# reference_2v5_LTC6655.net
KiCad netlist of a schematic drawn in Altium Designer
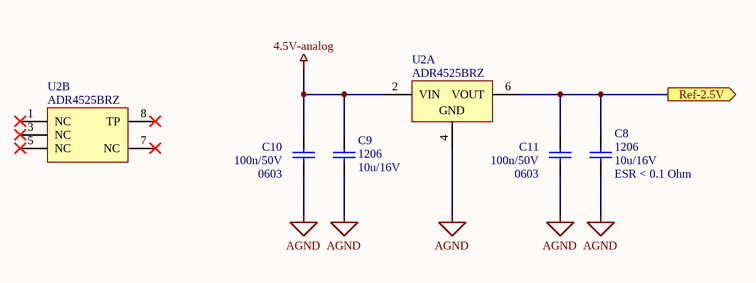
[diagram p0: reference_2v5_LTC6655.SchDoc]

(export (version "E")
  (design (tool "Eeschema 10.0.6"))
  (components
    (comp (ref "C8")
      (value "10u/16V")
      (footprint "SMD_Capacitor_1206")
      (description "Ceramic Cap Kemet COTS 10u/16V X7R 1206")
      (fields
        (field (name "MANUFACTURERPARTNUMBER") "C1206T106K4RACTU")
        (field (name "MANUFACTURER") "Kemet")
        (field (name "PACKGE") "1206")
      )
      (libsource (lib "capacitors") (part "Cer_C1206T106K4RACTU"))
    )
    (comp (ref "C9")
      (value "10u/16V")
      (footprint "SMD_Capacitor_1206")
      (description "Ceramic Cap Kemet COTS 10u/16V X7R 1206")
      (fields
        (field (name "MANUFACTURERPARTNUMBER") "C1206T106K4RACTU")
        (field (name "MANUFACTURER") "Kemet")
        (field (name "PACKGE") "1206")
      )
      (libsource (lib "capacitors") (part "Cer_C1206T106K4RACTU"))
    )
    (comp (ref "C10")
      (value "100n/50V")
      (footprint "SMD_Capacitor_0603")
      (description "Ceramic Cap Kemet COTS 100n/50V X7R 0603")
      (fields
        (field (name "MANUFACTURER") "Kemet")
        (field (name "MANUFACTURERPARTNUMBER") "C0603T104K5RALTU")
        (field (name "PACKAGE") "0603")
      )
      (libsource (lib "capacitors") (part "Cer_C0603T104K5RALTU"))
    )
    (comp (ref "C11")
      (value "100n/50V")
      (footprint "SMD_Capacitor_0603")
      (description "Ceramic Cap Kemet COTS 100n/50V X7R 0603")
      (fields
        (field (name "MANUFACTURER") "Kemet")
        (field (name "MANUFACTURERPARTNUMBER") "C0603T104K5RALTU")
        (field (name "PACKAGE") "0603")
      )
      (libsource (lib "capacitors") (part "Cer_C0603T104K5RALTU"))
    )
    (comp (ref "U2")
      (value "ADR4525BRZ")
      (footprint "ADI-R-8_N")
      (fields (field (name "MANUFACTURER") "Analog Devices"))
      (libsource (lib "Analog Devices Amplifiers and Linear Voltage References") (part "ADR4525BRZ"))
    )
  )
  (nets
    (net (code "1") (name "/Ref-2.5V") (class "Default")
      (node (ref "C11") (pin "1") (pinfunction "1_1") (pintype "passive"))
      (node (ref "C8") (pin "1") (pinfunction "1_1") (pintype "passive"))
      (node (ref "U2") (pin "6") (pinfunction "VOUT_6") (pintype "power_in"))
    )
    (net (code "2") (name "4.5V-analog") (class "Default")
      (node (ref "C10") (pin "1") (pinfunction "1_1") (pintype "passive"))
      (node (ref "C9") (pin "1") (pinfunction "1_1") (pintype "passive"))
      (node (ref "U2") (pin "2") (pinfunction "VIN_2") (pintype "power_in"))
    )
    (net (code "3") (name "AGND") (class "Default")
      (node (ref "C10") (pin "2") (pinfunction "2_2") (pintype "passive"))
      (node (ref "C11") (pin "2") (pinfunction "2_2") (pintype "passive"))
      (node (ref "C8") (pin "2") (pinfunction "2_2") (pintype "passive"))
      (node (ref "C9") (pin "2") (pinfunction "2_2") (pintype "passive"))
      (node (ref "U2") (pin "4") (pinfunction "GND_4") (pintype "power_in"))
    )
    (net (code "4") (name "unconnected-(U2B-NC-Pad1)") (class "Default")
      (node (ref "U2") (pin "1") (pinfunction "NC_1") (pintype "passive+no_connect"))
    )
    (net (code "5") (name "unconnected-(U2B-NC-Pad3)") (class "Default")
      (node (ref "U2") (pin "3") (pinfunction "NC_3") (pintype "passive+no_connect"))
    )
    (net (code "6") (name "unconnected-(U2B-NC-Pad5)") (class "Default")
      (node (ref "U2") (pin "5") (pinfunction "NC_5") (pintype "passive+no_connect"))
    )
    (net (code "7") (name "unconnected-(U2B-NC-Pad7)") (class "Default")
      (node (ref "U2") (pin "7") (pinfunction "NC_7") (pintype "passive+no_connect"))
    )
    (net (code "8") (name "unconnected-(U2B-TP-Pad8)") (class "Default")
      (node (ref "U2") (pin "8") (pinfunction "TP_8") (pintype "passive+no_connect"))
    )
  )
)
